# coqui-dip-simple.net
KiCad netlist of a schematic drawn in EAGLE
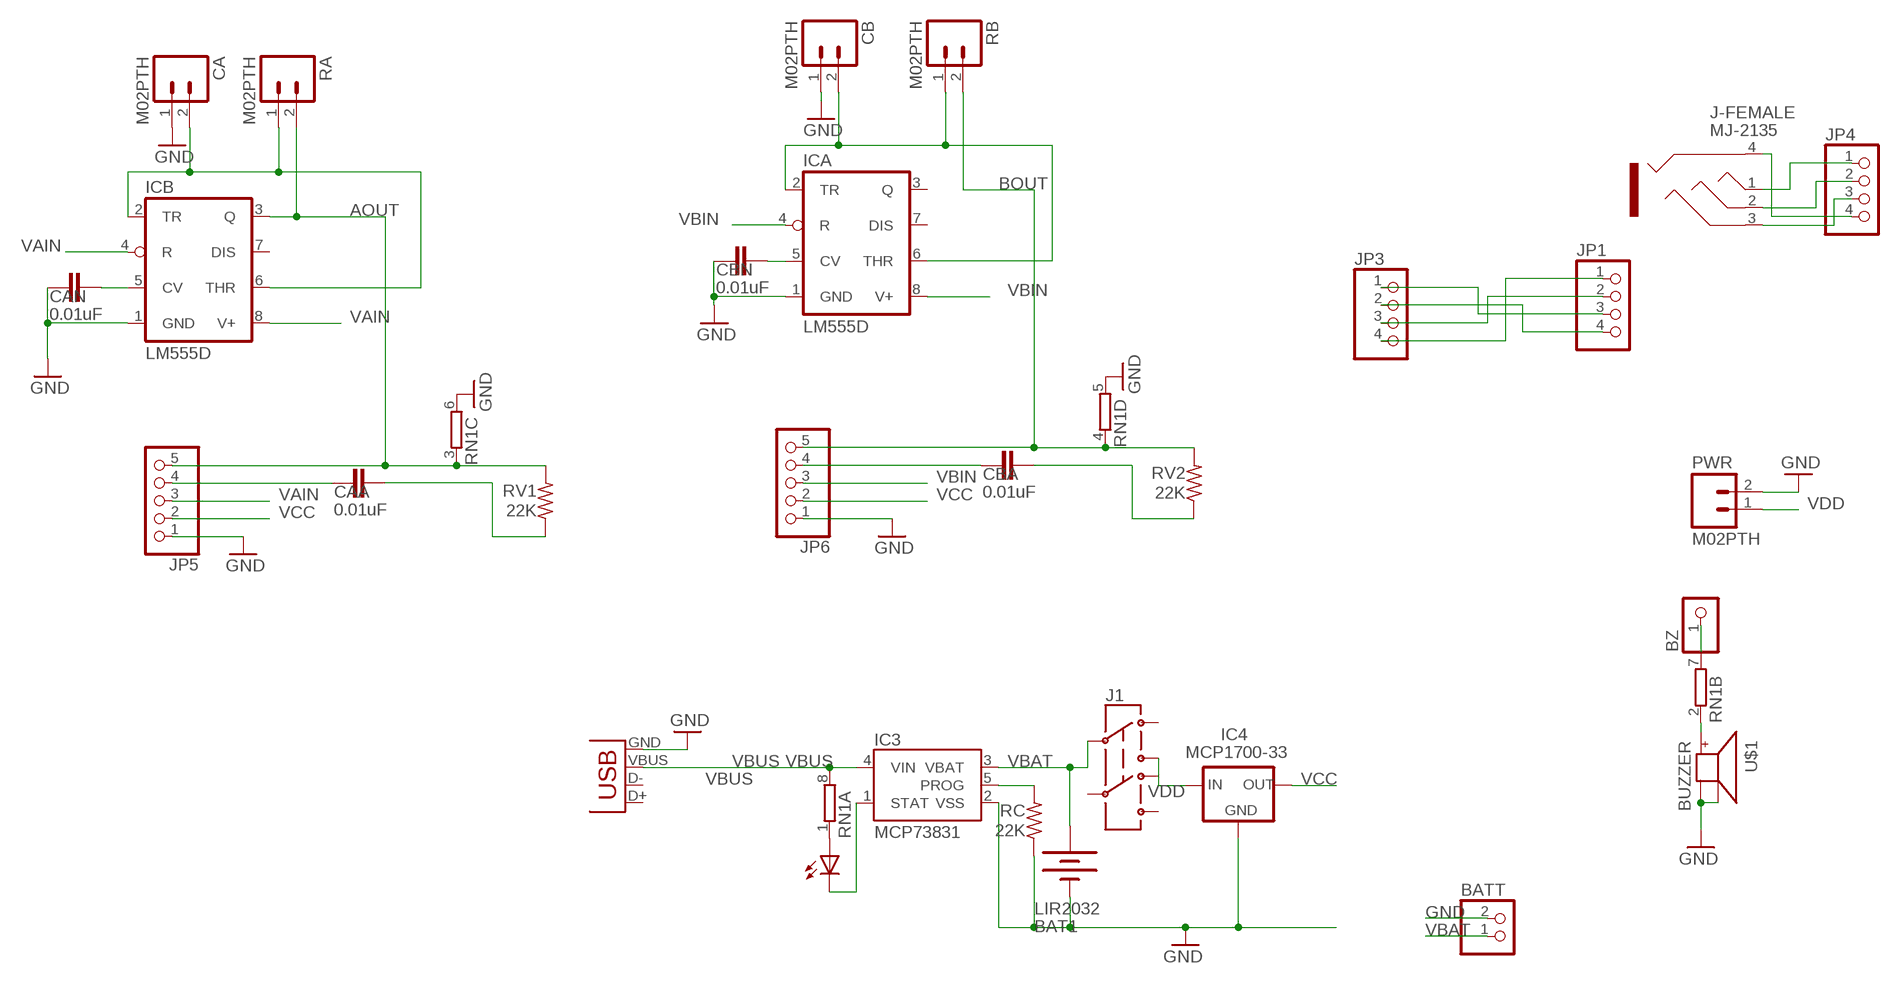
[diagram p0: schematic, sheet 1]

(export (version "E")
  (design (tool "Eeschema 10.0.6"))
  (components
    (comp (ref "BAT1")
      (value "LIR2032")
      (footprint "eagle-import:BATTCOM_20MM_PTH_SMT")
      (libsource (lib "eagle-import") (part "BATTERYBATTCOM_20MM_PTH_SMT"))
    )
    (comp (ref "BATT")
      (value "JST_2PIN-SMT-RA")
      (footprint "eagle-import:JST-PH-2-SMT-RA")
      (libsource (lib "eagle-import") (part "JST_2PIN-SMT-RA"))
    )
    (comp (ref "BZ")
      (value "PINHD-1X1")
      (footprint "eagle-import:1X01")
      (libsource (lib "eagle-import") (part "PINHD-1X1"))
    )
    (comp (ref "CA")
      (value "M02PTH")
      (footprint "eagle-import:1X02")
      (libsource (lib "eagle-import") (part "M02PTH"))
    )
    (comp (ref "CAA")
      (value "0.01uF")
      (footprint "eagle-import:C0805")
      (libsource (lib "eagle-import") (part "C-EUC0805"))
    )
    (comp (ref "CAN")
      (value "0.01uF")
      (footprint "eagle-import:C0805")
      (libsource (lib "eagle-import") (part "C-EUC0805"))
    )
    (comp (ref "CB")
      (value "M02PTH")
      (footprint "eagle-import:1X02")
      (libsource (lib "eagle-import") (part "M02PTH"))
    )
    (comp (ref "CBA")
      (value "0.01uF")
      (footprint "eagle-import:C0805")
      (libsource (lib "eagle-import") (part "C-EUC0805"))
    )
    (comp (ref "CBN")
      (value "0.01uF")
      (footprint "eagle-import:C0805")
      (libsource (lib "eagle-import") (part "C-EUC0805"))
    )
    (comp (ref "CHG")
      (value "0805")
      (footprint "eagle-import:CHIPLED_0805")
      (libsource (lib "eagle-import") (part "LEDCHIPLED_0805"))
    )
    (comp (ref "IC3")
      (value "MCP73831")
      (footprint "eagle-import:SOT23-5")
      (libsource (lib "eagle-import") (part "MCP73831"))
    )
    (comp (ref "IC4")
      (value "MCP1700-33")
      (footprint "eagle-import:SOT89")
      (libsource (lib "eagle-import") (part "MCP1700SOT89"))
    )
    (comp (ref "ICA")
      (value "LM555D")
      (footprint "eagle-import:SO08")
      (libsource (lib "eagle-import") (part "555DLM"))
    )
    (comp (ref "ICB")
      (value "LM555D")
      (footprint "eagle-import:SO08")
      (libsource (lib "eagle-import") (part "555DLM"))
    )
    (comp (ref "J-FEMALE")
      (value "MJ-2135")
      (footprint "eagle-import:MJ-2135")
      (libsource (lib "eagle-import") (part "MJ-2135"))
    )
    (comp (ref "J1")
      (value "AYZ0202")
      (footprint "eagle-import:AYZ0202")
      (libsource (lib "eagle-import") (part "AYZ0202"))
    )
    (comp (ref "JP1")
      (value "PINHD-1X4/90")
      (footprint "eagle-import:1X04_90")
      (libsource (lib "eagle-import") (part "trrs-dwb_PINHD-1X4/90"))
    )
    (comp (ref "JP3")
      (value "PINHD-1X4")
      (footprint "eagle-import:1X04")
      (libsource (lib "eagle-import") (part "PINHD-1X4"))
    )
    (comp (ref "JP4")
      (value "PINHD-1X4")
      (footprint "eagle-import:1X04")
      (libsource (lib "eagle-import") (part "PINHD-1X4"))
    )
    (comp (ref "JP5")
      (value "PINHD-1X5")
      (footprint "eagle-import:1X05")
      (libsource (lib "eagle-import") (part "PINHD-1X5"))
    )
    (comp (ref "JP6")
      (value "PINHD-1X5")
      (footprint "eagle-import:1X05")
      (libsource (lib "eagle-import") (part "PINHD-1X5"))
    )
    (comp (ref "PWR")
      (value "M02PTH")
      (footprint "eagle-import:1X02")
      (libsource (lib "eagle-import") (part "M02PTH"))
    )
    (comp (ref "RA")
      (value "M02PTH")
      (footprint "eagle-import:1X02")
      (libsource (lib "eagle-import") (part "M02PTH"))
    )
    (comp (ref "RB")
      (value "M02PTH")
      (footprint "eagle-import:1X02")
      (libsource (lib "eagle-import") (part "M02PTH"))
    )
    (comp (ref "RC")
      (value "22K")
      (footprint "eagle-import:R0805")
      (libsource (lib "eagle-import") (part "R-US_R0805"))
    )
    (comp (ref "RN1")
      (value "4R-NEXB38V")
      (footprint "eagle-import:EXB38V")
      (libsource (lib "eagle-import") (part "4R-NEXB38V"))
    )
    (comp (ref "RV1")
      (value "22K")
      (footprint "eagle-import:R0805")
      (libsource (lib "eagle-import") (part "R-US_R0805"))
    )
    (comp (ref "RV2")
      (value "22K")
      (footprint "eagle-import:R0805")
      (libsource (lib "eagle-import") (part "R-US_R0805"))
    )
    (comp (ref "U$1")
      (value "BUZZER")
      (footprint "eagle-import:SMT-8585-BUZZER")
      (libsource (lib "eagle-import") (part "BUZZER"))
    )
    (comp (ref "X1")
      (value "USBSMD")
      (footprint "eagle-import:USB-MINIB")
      (libsource (lib "eagle-import") (part "USBSMD"))
    )
  )
  (nets
    (net (code "1") (name "/AOUT") (class "Default")
      (node (ref "ICB") (pin "3") (pinfunction "Q_3") (pintype "output"))
      (node (ref "JP5") (pin "5") (pinfunction "5_5") (pintype "passive"))
      (node (ref "RA") (pin "2") (pinfunction "2_2") (pintype "passive"))
      (node (ref "RN1") (pin "3") (pinfunction "1_3") (pintype "passive"))
      (node (ref "RV1") (pin "2") (pinfunction "2_2") (pintype "passive"))
    )
    (net (code "2") (name "/BOUT") (class "Default")
      (node (ref "JP6") (pin "5") (pinfunction "5_5") (pintype "passive"))
      (node (ref "RB") (pin "2") (pinfunction "2_2") (pintype "passive"))
      (node (ref "RN1") (pin "4") (pinfunction "1_4") (pintype "passive"))
      (node (ref "RV2") (pin "2") (pinfunction "2_2") (pintype "passive"))
    )
    (net (code "3") (name "/VAIN") (class "Default")
      (node (ref "ICB") (pin "4") (pinfunction "R_4") (pintype "input"))
      (node (ref "ICB") (pin "8") (pinfunction "V+_8") (pintype "power_in"))
      (node (ref "JP5") (pin "3") (pinfunction "3_3") (pintype "passive"))
    )
    (net (code "4") (name "/VBAT") (class "Default")
      (node (ref "BAT1") (pin "P$2") (pinfunction "+_P$2") (pintype "power_in"))
      (node (ref "BATT") (pin "1") (pinfunction "2_1") (pintype "passive"))
      (node (ref "IC3") (pin "3") (pinfunction "VBAT_3") (pintype "power_in"))
      (node (ref "J1") (pin "2") (pinfunction "2_2") (pintype "bidirectional"))
    )
    (net (code "5") (name "/VBIN") (class "Default")
      (node (ref "ICA") (pin "4") (pinfunction "R_4") (pintype "input"))
      (node (ref "ICA") (pin "8") (pinfunction "V+_8") (pintype "power_in"))
      (node (ref "JP6") (pin "3") (pinfunction "3_3") (pintype "passive"))
    )
    (net (code "6") (name "/VBUS") (class "Default")
      (node (ref "IC3") (pin "4") (pinfunction "VIN_4") (pintype "power_in"))
      (node (ref "RN1") (pin "8") (pinfunction "2_8") (pintype "passive"))
      (node (ref "X1") (pin "VBUS") (pinfunction "VBUS_VBUS") (pintype "bidirectional"))
    )
    (net (code "7") (name "/VCC") (class "Default")
      (node (ref "IC4") (pin "3") (pinfunction "OUT_3") (pintype "passive"))
      (node (ref "JP5") (pin "2") (pinfunction "2_2") (pintype "passive"))
      (node (ref "JP6") (pin "2") (pinfunction "2_2") (pintype "passive"))
    )
    (net (code "8") (name "/VDD") (class "Default")
      (node (ref "IC4") (pin "2") (pinfunction "IN_2") (pintype "input"))
      (node (ref "J1") (pin "1") (pinfunction "3_1") (pintype "bidirectional"))
      (node (ref "PWR") (pin "1") (pinfunction "1_1") (pintype "passive"))
    )
    (net (code "9") (name "GND") (class "Default")
      (node (ref "BAT1") (pin "P$1") (pinfunction "-_P$1") (pintype "power_in"))
      (node (ref "BATT") (pin "2") (pinfunction "1_2") (pintype "passive"))
      (node (ref "CA") (pin "1") (pinfunction "1_1") (pintype "passive"))
      (node (ref "CAN") (pin "1") (pinfunction "1_1") (pintype "passive"))
      (node (ref "CB") (pin "1") (pinfunction "1_1") (pintype "passive"))
      (node (ref "CBN") (pin "1") (pinfunction "1_1") (pintype "passive"))
      (node (ref "IC3") (pin "2") (pinfunction "VSS_2") (pintype "power_in"))
      (node (ref "IC4") (pin "1") (pinfunction "GND_1") (pintype "input"))
      (node (ref "ICA") (pin "1") (pinfunction "GND_1") (pintype "power_in"))
      (node (ref "ICB") (pin "1") (pinfunction "GND_1") (pintype "power_in"))
      (node (ref "JP5") (pin "1") (pinfunction "1_1") (pintype "passive"))
      (node (ref "JP6") (pin "1") (pinfunction "1_1") (pintype "passive"))
      (node (ref "PWR") (pin "2") (pinfunction "2_2") (pintype "passive"))
      (node (ref "RC") (pin "1") (pinfunction "1_1") (pintype "passive"))
      (node (ref "RN1") (pin "5") (pinfunction "2_5") (pintype "passive"))
      (node (ref "RN1") (pin "6") (pinfunction "2_6") (pintype "passive"))
      (node (ref "U$1") (pin "-") (pinfunction "-_-") (pintype "passive"))
      (node (ref "U$1") (pin "A-") (pinfunction "A-_A-") (pintype "passive"))
      (node (ref "X1") (pin "GND") (pinfunction "GND_GND") (pintype "bidirectional"))
    )
    (net (code "10") (name "Net-(CAA-Pad1)") (class "Default")
      (node (ref "CAA") (pin "1") (pinfunction "1_1") (pintype "passive"))
      (node (ref "JP5") (pin "4") (pinfunction "4_4") (pintype "passive"))
    )
    (net (code "11") (name "Net-(CAA-Pad2)") (class "Default")
      (node (ref "CAA") (pin "2") (pinfunction "2_2") (pintype "passive"))
      (node (ref "RV1") (pin "1") (pinfunction "1_1") (pintype "passive"))
    )
    (net (code "12") (name "Net-(CBA-Pad1)") (class "Default")
      (node (ref "CBA") (pin "1") (pinfunction "1_1") (pintype "passive"))
      (node (ref "JP6") (pin "4") (pinfunction "4_4") (pintype "passive"))
    )
    (net (code "13") (name "Net-(CBA-Pad2)") (class "Default")
      (node (ref "CBA") (pin "2") (pinfunction "2_2") (pintype "passive"))
      (node (ref "RV2") (pin "1") (pinfunction "1_1") (pintype "passive"))
    )
    (net (code "14") (name "Net-(CHG-PadA)") (class "Default")
      (node (ref "CHG") (pin "A") (pinfunction "A_A") (pintype "passive"))
      (node (ref "RN1") (pin "1") (pinfunction "1_1") (pintype "passive"))
    )
    (net (code "15") (name "Net-(IC3-PROG)") (class "Default")
      (node (ref "IC3") (pin "5") (pinfunction "PROG_5") (pintype "input"))
      (node (ref "RC") (pin "2") (pinfunction "2_2") (pintype "passive"))
    )
    (net (code "16") (name "Net-(IC3-STAT)") (class "Default")
      (node (ref "CHG") (pin "C") (pinfunction "C_C") (pintype "passive"))
      (node (ref "IC3") (pin "1") (pinfunction "STAT_1") (pintype "output"))
    )
    (net (code "17") (name "Net-(ICA-CV)") (class "Default")
      (node (ref "CBN") (pin "2") (pinfunction "2_2") (pintype "passive"))
      (node (ref "ICA") (pin "5") (pinfunction "CV_5") (pintype "input"))
    )
    (net (code "18") (name "Net-(ICA-THR)") (class "Default")
      (node (ref "CB") (pin "2") (pinfunction "2_2") (pintype "passive"))
      (node (ref "ICA") (pin "2") (pinfunction "TR_2") (pintype "input"))
      (node (ref "ICA") (pin "6") (pinfunction "THR_6") (pintype "input"))
      (node (ref "RB") (pin "1") (pinfunction "1_1") (pintype "passive"))
    )
    (net (code "19") (name "Net-(ICB-CV)") (class "Default")
      (node (ref "CAN") (pin "2") (pinfunction "2_2") (pintype "passive"))
      (node (ref "ICB") (pin "5") (pinfunction "CV_5") (pintype "input"))
    )
    (net (code "20") (name "Net-(ICB-THR)") (class "Default")
      (node (ref "CA") (pin "2") (pinfunction "2_2") (pintype "passive"))
      (node (ref "ICB") (pin "2") (pinfunction "TR_2") (pintype "input"))
      (node (ref "ICB") (pin "6") (pinfunction "THR_6") (pintype "input"))
      (node (ref "RA") (pin "1") (pinfunction "1_1") (pintype "passive"))
    )
    (net (code "21") (name "Net-(J-FEMALE-Pad1)") (class "Default")
      (node (ref "J-FEMALE") (pin "1") (pinfunction "1_1") (pintype "passive"))
      (node (ref "JP4") (pin "1") (pinfunction "1_1") (pintype "passive"))
    )
    (net (code "22") (name "Net-(J-FEMALE-Pad2)") (class "Default")
      (node (ref "J-FEMALE") (pin "2") (pinfunction "2_2") (pintype "passive"))
      (node (ref "JP4") (pin "2") (pinfunction "2_2") (pintype "passive"))
    )
    (net (code "23") (name "Net-(J-FEMALE-Pad3)") (class "Default")
      (node (ref "J-FEMALE") (pin "3") (pinfunction "3_3") (pintype "passive"))
      (node (ref "JP4") (pin "3") (pinfunction "3_3") (pintype "passive"))
    )
    (net (code "24") (name "Net-(J-FEMALE-Pad4)") (class "Default")
      (node (ref "J-FEMALE") (pin "4") (pinfunction "4_4") (pintype "passive"))
      (node (ref "JP4") (pin "4") (pinfunction "4_4") (pintype "passive"))
    )
    (net (code "25") (name "Net-(JP1-Pad1)") (class "Default")
      (node (ref "JP1") (pin "1") (pinfunction "1_1") (pintype "passive"))
      (node (ref "JP3") (pin "4") (pinfunction "4_4") (pintype "passive"))
    )
    (net (code "26") (name "Net-(JP1-Pad2)") (class "Default")
      (node (ref "JP1") (pin "2") (pinfunction "2_2") (pintype "passive"))
      (node (ref "JP3") (pin "3") (pinfunction "3_3") (pintype "passive"))
    )
    (net (code "27") (name "Net-(JP1-Pad3)") (class "Default")
      (node (ref "JP1") (pin "3") (pinfunction "3_3") (pintype "passive"))
      (node (ref "JP3") (pin "1") (pinfunction "1_1") (pintype "passive"))
    )
    (net (code "28") (name "Net-(JP1-Pad4)") (class "Default")
      (node (ref "JP1") (pin "4") (pinfunction "4_4") (pintype "passive"))
      (node (ref "JP3") (pin "2") (pinfunction "2_2") (pintype "passive"))
    )
    (net (code "29") (name "Net-(RN1B-1)") (class "Default")
      (node (ref "RN1") (pin "2") (pinfunction "1_2") (pintype "passive"))
      (node (ref "U$1") (pin "+") (pinfunction "+_+") (pintype "passive"))
    )
    (net (code "30") (name "Net-(RN1B-2)") (class "Default")
      (node (ref "BZ") (pin "1") (pinfunction "1_1") (pintype "passive"))
      (node (ref "RN1") (pin "7") (pinfunction "2_7") (pintype "passive"))
    )
    (net (code "31") (name "unconnected-(ICA-DIS-Pad7)") (class "Default")
      (node (ref "ICA") (pin "7") (pinfunction "DIS_7") (pintype "input"))
    )
    (net (code "32") (name "unconnected-(ICA-Q-Pad3)") (class "Default")
      (node (ref "ICA") (pin "3") (pinfunction "Q_3") (pintype "output"))
    )
    (net (code "33") (name "unconnected-(ICB-DIS-Pad7)") (class "Default")
      (node (ref "ICB") (pin "7") (pinfunction "DIS_7") (pintype "input"))
    )
    (net (code "34") (name "unconnected-(J1-1-Pad3)") (class "Default")
      (node (ref "J1") (pin "3") (pinfunction "1_3") (pintype "bidirectional"))
    )
    (net (code "35") (name "unconnected-(J1-4-Pad6)") (class "Default")
      (node (ref "J1") (pin "6") (pinfunction "4_6") (pintype "bidirectional"))
    )
    (net (code "36") (name "unconnected-(J1-6-Pad4)") (class "Default")
      (node (ref "J1") (pin "4") (pinfunction "6_4") (pintype "bidirectional"))
    )
    (net (code "37") (name "unconnected-(J1-Pad5)") (class "Default")
      (node (ref "J1") (pin "5") (pinfunction "5_5") (pintype "bidirectional"))
    )
    (net (code "38") (name "unconnected-(X1-PadD+)") (class "Default")
      (node (ref "X1") (pin "D+") (pinfunction "D+_D+") (pintype "bidirectional"))
    )
    (net (code "39") (name "unconnected-(X1-PadD-)") (class "Default")
      (node (ref "X1") (pin "D-") (pinfunction "D-_D-") (pintype "bidirectional"))
    )
  )
)
